# POWER_TS.net
KiCad netlist of a schematic drawn in Altium Designer
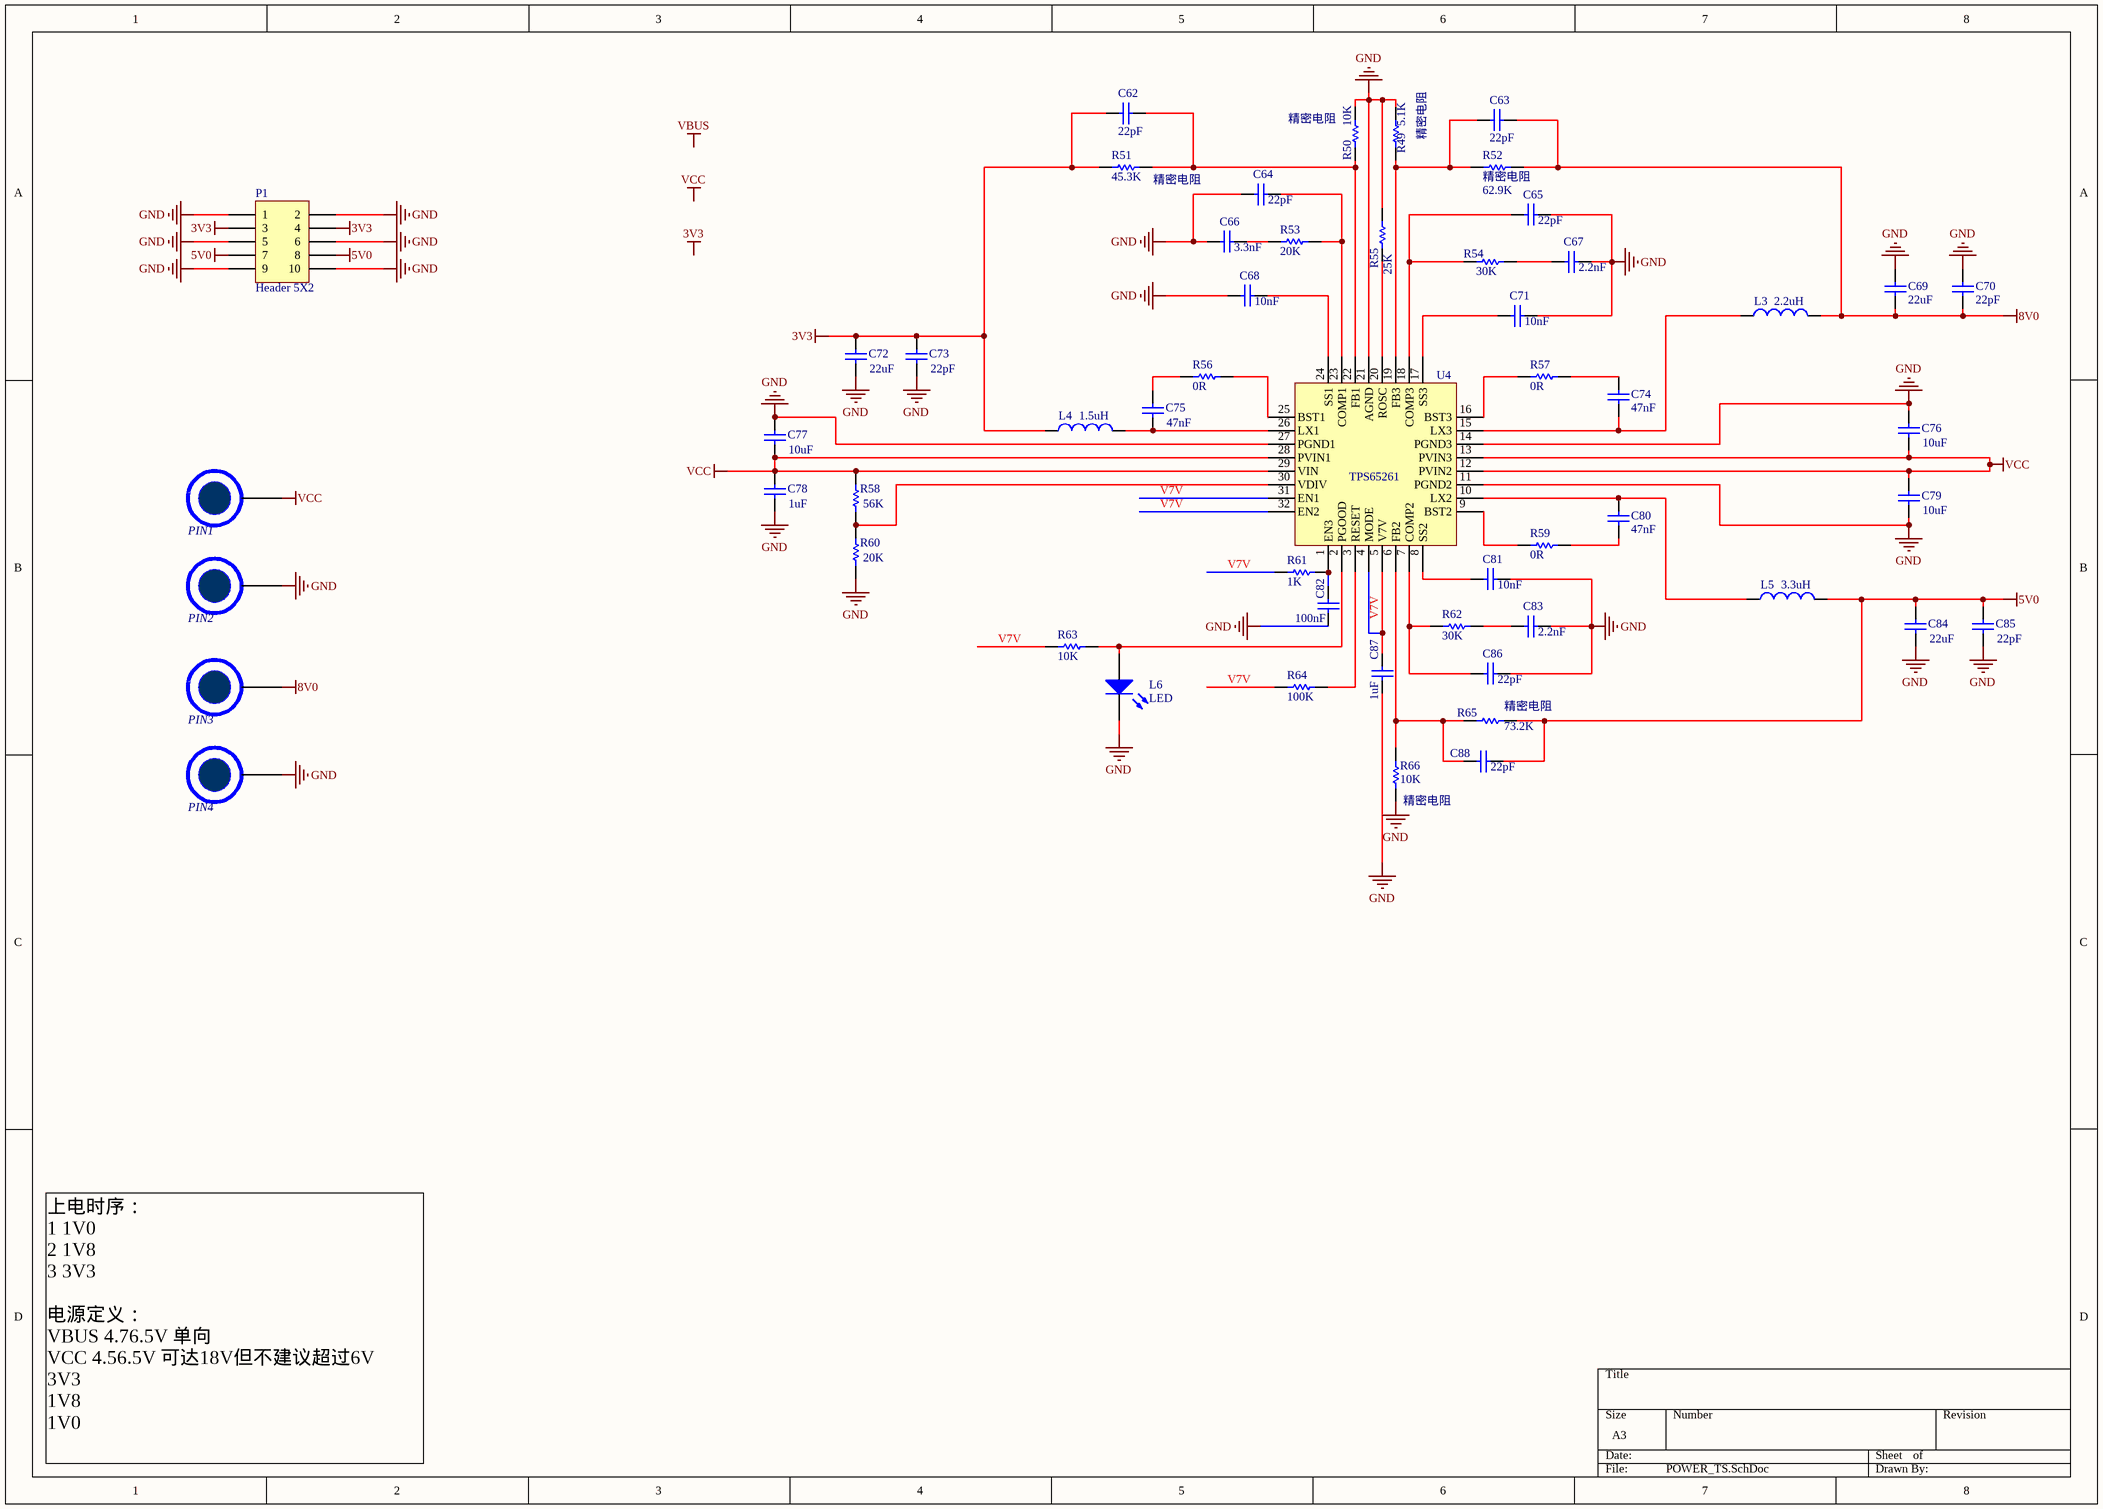
[diagram p0: POWER_TS.SchDoc]

(export (version "E")
  (design (tool "Eeschema 10.0.6"))
  (components
    (comp (ref "C62")
      (value "22pF")
      (footprint "0402")
      (description "贴片电容")
      (fields (field (name "Comment") "Cap") (field (name "PUBLISHER") "Altium Limited"))
      (libsource (lib "Sparks") (part "Cap"))
    )
    (comp (ref "C63")
      (value "22pF")
      (footprint "0402")
      (description "贴片电容")
      (fields (field (name "Comment") "Cap") (field (name "PUBLISHER") "Altium Limited"))
      (libsource (lib "Sparks") (part "Cap"))
    )
    (comp (ref "C64")
      (value "22pF")
      (footprint "0402")
      (description "贴片电容")
      (fields (field (name "Comment") "Cap") (field (name "PUBLISHER") "Altium Limited"))
      (libsource (lib "Sparks") (part "Cap"))
    )
    (comp (ref "C65")
      (value "22pF")
      (footprint "0402")
      (description "贴片电容")
      (fields (field (name "Comment") "Cap") (field (name "PUBLISHER") "Altium Limited"))
      (libsource (lib "Sparks") (part "Cap"))
    )
    (comp (ref "C66")
      (value "3.3nF")
      (footprint "0402")
      (description "贴片电容")
      (fields (field (name "Comment") "Cap") (field (name "PUBLISHER") "Altium Limited"))
      (libsource (lib "Sparks") (part "Cap"))
    )
    (comp (ref "C67")
      (value "2.2nF")
      (footprint "0402")
      (description "贴片电容")
      (fields (field (name "Comment") "Cap") (field (name "PUBLISHER") "Altium Limited"))
      (libsource (lib "Sparks") (part "Cap"))
    )
    (comp (ref "C68")
      (value "10nF")
      (footprint "0402")
      (description "贴片电容")
      (fields (field (name "Comment") "Cap") (field (name "PUBLISHER") "Altium Limited"))
      (libsource (lib "Sparks") (part "Cap"))
    )
    (comp (ref "C69")
      (value "22uF")
      (footprint "1206")
      (description "贴片电容")
      (fields (field (name "Comment") "Cap") (field (name "PUBLISHER") "Altium Limited"))
      (libsource (lib "Sparks") (part "Cap"))
    )
    (comp (ref "C70")
      (value "22pF")
      (footprint "0402")
      (description "贴片电容")
      (fields (field (name "Comment") "Cap") (field (name "PUBLISHER") "Altium Limited"))
      (libsource (lib "Sparks") (part "Cap"))
    )
    (comp (ref "C71")
      (value "10nF")
      (footprint "0402")
      (description "贴片电容")
      (fields (field (name "Comment") "Cap") (field (name "PUBLISHER") "Altium Limited"))
      (libsource (lib "Sparks") (part "Cap"))
    )
    (comp (ref "C72")
      (value "22uF")
      (footprint "1206")
      (description "贴片电容")
      (fields (field (name "Comment") "Cap") (field (name "PUBLISHER") "Altium Limited"))
      (libsource (lib "Sparks") (part "Cap"))
    )
    (comp (ref "C73")
      (value "22pF")
      (footprint "0402")
      (description "贴片电容")
      (fields (field (name "Comment") "Cap") (field (name "PUBLISHER") "Altium Limited"))
      (libsource (lib "Sparks") (part "Cap"))
    )
    (comp (ref "C74")
      (value "47nF")
      (footprint "0402")
      (description "贴片电容")
      (fields (field (name "Comment") "Cap") (field (name "PUBLISHER") "Altium Limited"))
      (libsource (lib "Sparks") (part "Cap"))
    )
    (comp (ref "C75")
      (value "47nF")
      (footprint "0402")
      (description "贴片电容")
      (fields (field (name "Comment") "Cap") (field (name "PUBLISHER") "Altium Limited"))
      (libsource (lib "Sparks") (part "Cap"))
    )
    (comp (ref "C76")
      (value "10uF")
      (footprint "1206")
      (description "贴片电容")
      (fields (field (name "Comment") "Cap") (field (name "PUBLISHER") "Altium Limited"))
      (libsource (lib "Sparks") (part "Cap"))
    )
    (comp (ref "C77")
      (value "10uF")
      (footprint "1206")
      (description "贴片电容")
      (fields (field (name "Comment") "Cap") (field (name "PUBLISHER") "Altium Limited"))
      (libsource (lib "Sparks") (part "Cap"))
    )
    (comp (ref "C78")
      (value "1uF")
      (footprint "1608[0603]")
      (description "贴片电容")
      (fields (field (name "Comment") "Cap") (field (name "PUBLISHER") "Altium Limited"))
      (libsource (lib "Sparks") (part "Cap"))
    )
    (comp (ref "C79")
      (value "10uF")
      (footprint "1206")
      (description "贴片电容")
      (fields (field (name "Comment") "Cap") (field (name "PUBLISHER") "Altium Limited"))
      (libsource (lib "Sparks") (part "Cap"))
    )
    (comp (ref "C80")
      (value "47nF")
      (footprint "0402")
      (description "贴片电容")
      (fields (field (name "Comment") "Cap") (field (name "PUBLISHER") "Altium Limited"))
      (libsource (lib "Sparks") (part "Cap"))
    )
    (comp (ref "C81")
      (value "10nF")
      (footprint "0402")
      (description "贴片电容")
      (fields (field (name "Comment") "Cap") (field (name "PUBLISHER") "Altium Limited"))
      (libsource (lib "Sparks") (part "Cap"))
    )
    (comp (ref "C82")
      (value "100nF")
      (footprint "0402")
      (description "贴片电容")
      (fields (field (name "Comment") "Cap") (field (name "PUBLISHER") "Altium Limited"))
      (libsource (lib "Sparks") (part "Cap"))
    )
    (comp (ref "C83")
      (value "2.2nF")
      (footprint "0402")
      (description "贴片电容")
      (fields (field (name "Comment") "Cap") (field (name "PUBLISHER") "Altium Limited"))
      (libsource (lib "Sparks") (part "Cap"))
    )
    (comp (ref "C84")
      (value "22uF")
      (footprint "1206")
      (description "贴片电容")
      (fields (field (name "Comment") "Cap") (field (name "PUBLISHER") "Altium Limited"))
      (libsource (lib "Sparks") (part "Cap"))
    )
    (comp (ref "C85")
      (value "22pF")
      (footprint "0402")
      (description "贴片电容")
      (fields (field (name "Comment") "Cap") (field (name "PUBLISHER") "Altium Limited"))
      (libsource (lib "Sparks") (part "Cap"))
    )
    (comp (ref "C86")
      (value "22pF")
      (footprint "0402")
      (description "贴片电容")
      (fields (field (name "Comment") "Cap") (field (name "PUBLISHER") "Altium Limited"))
      (libsource (lib "Sparks") (part "Cap"))
    )
    (comp (ref "C87")
      (value "1uF")
      (footprint "1608[0603]")
      (description "贴片电容")
      (fields (field (name "Comment") "Cap") (field (name "PUBLISHER") "Altium Limited"))
      (libsource (lib "Sparks") (part "Cap"))
    )
    (comp (ref "C88")
      (value "22pF")
      (footprint "0402")
      (description "贴片电容")
      (fields (field (name "Comment") "Cap") (field (name "PUBLISHER") "Altium Limited"))
      (libsource (lib "Sparks") (part "Cap"))
    )
    (comp (ref "L3")
      (value "2.2uH")
      (footprint "2220")
      (description "Inductor")
      (fields (field (name "PUBLISHER") "Altium Limited"))
      (libsource (lib "Miscellaneous Devices") (part "Inductor"))
    )
    (comp (ref "L4")
      (value "1.5uH")
      (footprint "C2012")
      (description "Inductor")
      (fields (field (name "PUBLISHER") "Altium Limited"))
      (libsource (lib "Miscellaneous Devices") (part "Inductor"))
    )
    (comp (ref "L5")
      (value "3.3uH")
      (footprint "C2012")
      (description "Inductor")
      (fields (field (name "PUBLISHER") "Altium Limited"))
      (libsource (lib "Miscellaneous Devices") (part "Inductor"))
    )
    (comp (ref "L6") (value "LED") (footprint "1608[0603]") (libsource (lib "Sparks") (part "LED")))
    (comp (ref "P1")
      (value "Header 5X2")
      (footprint "HDR2X5")
      (description "Header, 5-Pin, Dual row")
      (fields (field (name "PUBLISHER") "Altium Limited"))
      (libsource (lib "Sparks") (part "Header 5X2"))
    )
    (comp (ref "PIN1") (value "PIN") (footprint "PIN") (libsource (lib "2号库") (part "PIN")))
    (comp (ref "PIN2") (value "PIN") (footprint "PIN") (libsource (lib "2号库") (part "PIN")))
    (comp (ref "PIN3") (value "PIN") (footprint "PIN") (libsource (lib "2号库") (part "PIN")))
    (comp (ref "PIN4") (value "PIN") (footprint "PIN") (libsource (lib "2号库") (part "PIN")))
    (comp (ref "R49")
      (value "精密电阻")
      (footprint "1608[0603]")
      (description "贴片电阻")
      (fields (field (name "ALTIUM_VALUE") "5.1K") (field (name "PUBLISHER") "Altium Limited"))
      (libsource (lib "Sparks") (part "Res"))
    )
    (comp (ref "R50")
      (value "精密电阻")
      (footprint "1608[0603]")
      (description "贴片电阻")
      (fields (field (name "ALTIUM_VALUE") "10K") (field (name "PUBLISHER") "Altium Limited"))
      (libsource (lib "Sparks") (part "Res"))
    )
    (comp (ref "R51")
      (value "精密电阻")
      (footprint "R2012")
      (description "贴片电阻")
      (fields (field (name "ALTIUM_VALUE") "45.3K") (field (name "PUBLISHER") "Altium Limited"))
      (libsource (lib "Sparks") (part "Res"))
    )
    (comp (ref "R52")
      (value "精密电阻")
      (footprint "R2012")
      (description "贴片电阻")
      (fields (field (name "ALTIUM_VALUE") "62.9K") (field (name "PUBLISHER") "Altium Limited"))
      (libsource (lib "Sparks") (part "Res"))
    )
    (comp (ref "R53")
      (value "20K")
      (footprint "0402")
      (description "贴片电阻")
      (fields (field (name "Comment") "Res") (field (name "PUBLISHER") "Altium Limited"))
      (libsource (lib "Sparks") (part "Res"))
    )
    (comp (ref "R54")
      (value "30K")
      (footprint "0402")
      (description "贴片电阻")
      (fields (field (name "Comment") "Res") (field (name "PUBLISHER") "Altium Limited"))
      (libsource (lib "Sparks") (part "Res"))
    )
    (comp (ref "R55")
      (value "25K")
      (footprint "0402")
      (description "贴片电阻")
      (fields (field (name "Comment") "Res") (field (name "PUBLISHER") "Altium Limited"))
      (libsource (lib "Sparks") (part "Res"))
    )
    (comp (ref "R56")
      (value "0R")
      (footprint "0402")
      (description "贴片电阻")
      (fields (field (name "Comment") "Res") (field (name "PUBLISHER") "Altium Limited"))
      (libsource (lib "Sparks") (part "Res"))
    )
    (comp (ref "R57")
      (value "0R")
      (footprint "0402")
      (description "贴片电阻")
      (fields (field (name "Comment") "Res") (field (name "PUBLISHER") "Altium Limited"))
      (libsource (lib "Sparks") (part "Res"))
    )
    (comp (ref "R58")
      (value "56K")
      (footprint "0402")
      (description "贴片电阻")
      (fields (field (name "Comment") "Res") (field (name "PUBLISHER") "Altium Limited"))
      (libsource (lib "Sparks") (part "Res"))
    )
    (comp (ref "R59")
      (value "0R")
      (footprint "0402")
      (description "贴片电阻")
      (fields (field (name "Comment") "Res") (field (name "PUBLISHER") "Altium Limited"))
      (libsource (lib "Sparks") (part "Res"))
    )
    (comp (ref "R60")
      (value "20K")
      (footprint "0402")
      (description "贴片电阻")
      (fields (field (name "Comment") "Res") (field (name "PUBLISHER") "Altium Limited"))
      (libsource (lib "Sparks") (part "Res"))
    )
    (comp (ref "R61")
      (value "1K")
      (footprint "0402")
      (description "贴片电阻")
      (fields (field (name "Comment") "Res") (field (name "PUBLISHER") "Altium Limited"))
      (libsource (lib "Sparks") (part "Res"))
    )
    (comp (ref "R62")
      (value "30K")
      (footprint "0402")
      (description "贴片电阻")
      (fields (field (name "Comment") "Res") (field (name "PUBLISHER") "Altium Limited"))
      (libsource (lib "Sparks") (part "Res"))
    )
    (comp (ref "R63")
      (value "10K")
      (footprint "0402")
      (description "贴片电阻")
      (fields (field (name "Comment") "Res") (field (name "PUBLISHER") "Altium Limited"))
      (libsource (lib "Sparks") (part "Res"))
    )
    (comp (ref "R64")
      (value "100K")
      (footprint "0402")
      (description "贴片电阻")
      (fields (field (name "Comment") "Res") (field (name "PUBLISHER") "Altium Limited"))
      (libsource (lib "Sparks") (part "Res"))
    )
    (comp (ref "R65")
      (value "精密电阻")
      (footprint "1608[0603]")
      (description "贴片电阻")
      (fields (field (name "ALTIUM_VALUE") "73.2K") (field (name "PUBLISHER") "Altium Limited"))
      (libsource (lib "Sparks") (part "Res"))
    )
    (comp (ref "R66")
      (value "精密电阻")
      (footprint "1608[0603]")
      (description "贴片电阻")
      (fields (field (name "ALTIUM_VALUE") "10K") (field (name "PUBLISHER") "Altium Limited"))
      (libsource (lib "Sparks") (part "Res"))
    )
    (comp (ref "U4")
      (value "TPS65261")
      (footprint "QFN50P500X500X100_HS-33N")
      (libsource (lib "2号库") (part "TPS65261"))
    )
  )
  (nets
    (net (code "1") (name "/V7V") (class "Default")
      (node (ref "C87") (pin "2") (pinfunction "2_2") (pintype "passive"))
      (node (ref "R61") (pin "1") (pinfunction "1_1") (pintype "passive"))
      (node (ref "R63") (pin "2") (pinfunction "2_2") (pintype "passive"))
      (node (ref "R64") (pin "2") (pinfunction "2_2") (pintype "passive"))
      (node (ref "U4") (pin "31") (pinfunction "EN1_31") (pintype "passive"))
      (node (ref "U4") (pin "32") (pinfunction "EN2_32") (pintype "passive"))
      (node (ref "U4") (pin "4") (pinfunction "MODE_4") (pintype "passive"))
      (node (ref "U4") (pin "5") (pinfunction "V7V_5") (pintype "passive"))
    )
    (net (code "2") (name "3V3") (class "Default")
      (node (ref "C62") (pin "2") (pinfunction "2_2") (pintype "passive"))
      (node (ref "C72") (pin "2") (pinfunction "2_2") (pintype "passive"))
      (node (ref "C73") (pin "2") (pinfunction "2_2") (pintype "passive"))
      (node (ref "L4") (pin "1") (pinfunction "1_1") (pintype "passive"))
      (node (ref "P1") (pin "3") (pinfunction "3_3") (pintype "passive"))
      (node (ref "P1") (pin "4") (pinfunction "4_4") (pintype "passive"))
      (node (ref "R51") (pin "2") (pinfunction "2_2") (pintype "passive"))
    )
    (net (code "3") (name "5V0") (class "Default")
      (node (ref "C84") (pin "2") (pinfunction "2_2") (pintype "passive"))
      (node (ref "C85") (pin "2") (pinfunction "2_2") (pintype "passive"))
      (node (ref "C88") (pin "2") (pinfunction "2_2") (pintype "passive"))
      (node (ref "L5") (pin "2") (pinfunction "2_2") (pintype "passive"))
      (node (ref "P1") (pin "7") (pinfunction "7_7") (pintype "passive"))
      (node (ref "P1") (pin "8") (pinfunction "8_8") (pintype "passive"))
      (node (ref "R65") (pin "1") (pinfunction "1_1") (pintype "passive"))
    )
    (net (code "4") (name "8V0") (class "Default")
      (node (ref "C63") (pin "1") (pinfunction "1_1") (pintype "passive"))
      (node (ref "C69") (pin "2") (pinfunction "2_2") (pintype "passive"))
      (node (ref "C70") (pin "2") (pinfunction "2_2") (pintype "passive"))
      (node (ref "L3") (pin "2") (pinfunction "2_2") (pintype "passive"))
      (node (ref "PIN3") (pin "1") (pinfunction "PIN_1") (pintype "passive"))
      (node (ref "R52") (pin "1") (pinfunction "1_1") (pintype "passive"))
    )
    (net (code "5") (name "GND") (class "Default")
      (node (ref "C64") (pin "1") (pinfunction "1_1") (pintype "passive"))
      (node (ref "C65") (pin "2") (pinfunction "2_2") (pintype "passive"))
      (node (ref "C66") (pin "1") (pinfunction "1_1") (pintype "passive"))
      (node (ref "C67") (pin "2") (pinfunction "2_2") (pintype "passive"))
      (node (ref "C68") (pin "1") (pinfunction "1_1") (pintype "passive"))
      (node (ref "C69") (pin "1") (pinfunction "1_1") (pintype "passive"))
      (node (ref "C70") (pin "1") (pinfunction "1_1") (pintype "passive"))
      (node (ref "C71") (pin "2") (pinfunction "2_2") (pintype "passive"))
      (node (ref "C72") (pin "1") (pinfunction "1_1") (pintype "passive"))
      (node (ref "C73") (pin "1") (pinfunction "1_1") (pintype "passive"))
      (node (ref "C76") (pin "2") (pinfunction "2_2") (pintype "passive"))
      (node (ref "C77") (pin "2") (pinfunction "2_2") (pintype "passive"))
      (node (ref "C78") (pin "1") (pinfunction "1_1") (pintype "passive"))
      (node (ref "C79") (pin "1") (pinfunction "1_1") (pintype "passive"))
      (node (ref "C81") (pin "1") (pinfunction "1_1") (pintype "passive"))
      (node (ref "C82") (pin "1") (pinfunction "1_1") (pintype "passive"))
      (node (ref "C83") (pin "1") (pinfunction "1_1") (pintype "passive"))
      (node (ref "C84") (pin "1") (pinfunction "1_1") (pintype "passive"))
      (node (ref "C85") (pin "1") (pinfunction "1_1") (pintype "passive"))
      (node (ref "C86") (pin "2") (pinfunction "2_2") (pintype "passive"))
      (node (ref "C87") (pin "1") (pinfunction "1_1") (pintype "passive"))
      (node (ref "L6") (pin "2") (pinfunction "K_2") (pintype "passive"))
      (node (ref "P1") (pin "1") (pinfunction "1_1") (pintype "passive"))
      (node (ref "P1") (pin "10") (pinfunction "10_10") (pintype "passive"))
      (node (ref "P1") (pin "2") (pinfunction "2_2") (pintype "passive"))
      (node (ref "P1") (pin "5") (pinfunction "5_5") (pintype "passive"))
      (node (ref "P1") (pin "6") (pinfunction "6_6") (pintype "passive"))
      (node (ref "P1") (pin "9") (pinfunction "9_9") (pintype "passive"))
      (node (ref "PIN2") (pin "1") (pinfunction "PIN_1") (pintype "passive"))
      (node (ref "PIN4") (pin "1") (pinfunction "PIN_1") (pintype "passive"))
      (node (ref "R49") (pin "1") (pinfunction "1_1") (pintype "passive"))
      (node (ref "R50") (pin "1") (pinfunction "1_1") (pintype "passive"))
      (node (ref "R55") (pin "2") (pinfunction "2_2") (pintype "passive"))
      (node (ref "R60") (pin "1") (pinfunction "1_1") (pintype "passive"))
      (node (ref "R66") (pin "1") (pinfunction "1_1") (pintype "passive"))
      (node (ref "U4") (pin "11") (pinfunction "PGND2_11") (pintype "passive"))
      (node (ref "U4") (pin "14") (pinfunction "PGND3_14") (pintype "passive"))
      (node (ref "U4") (pin "21") (pinfunction "AGND_21") (pintype "passive"))
      (node (ref "U4") (pin "27") (pinfunction "PGND1_27") (pintype "passive"))
    )
    (net (code "6") (name "Net-(C66-Pad2)") (class "Default")
      (node (ref "C66") (pin "2") (pinfunction "2_2") (pintype "passive"))
      (node (ref "R53") (pin "1") (pinfunction "1_1") (pintype "passive"))
    )
    (net (code "7") (name "Net-(C67-Pad1)") (class "Default")
      (node (ref "C67") (pin "1") (pinfunction "1_1") (pintype "passive"))
      (node (ref "R54") (pin "2") (pinfunction "2_2") (pintype "passive"))
    )
    (net (code "8") (name "Net-(C74-Pad1)") (class "Default")
      (node (ref "C74") (pin "1") (pinfunction "1_1") (pintype "passive"))
      (node (ref "R57") (pin "1") (pinfunction "1_1") (pintype "passive"))
    )
    (net (code "9") (name "Net-(C75-Pad2)") (class "Default")
      (node (ref "C75") (pin "2") (pinfunction "2_2") (pintype "passive"))
      (node (ref "R56") (pin "2") (pinfunction "2_2") (pintype "passive"))
    )
    (net (code "10") (name "Net-(C80-Pad2)") (class "Default")
      (node (ref "C80") (pin "2") (pinfunction "2_2") (pintype "passive"))
      (node (ref "R59") (pin "1") (pinfunction "1_1") (pintype "passive"))
    )
    (net (code "11") (name "Net-(C83-Pad2)") (class "Default")
      (node (ref "C83") (pin "2") (pinfunction "2_2") (pintype "passive"))
      (node (ref "R62") (pin "2") (pinfunction "2_2") (pintype "passive"))
    )
    (net (code "12") (name "Net-(L6-A)") (class "Default")
      (node (ref "L6") (pin "1") (pinfunction "A_1") (pintype "passive"))
      (node (ref "R63") (pin "1") (pinfunction "1_1") (pintype "passive"))
      (node (ref "U4") (pin "2") (pinfunction "PGOOD_2") (pintype "passive"))
    )
    (net (code "13") (name "Net-(U4-BST1)") (class "Default")
      (node (ref "R56") (pin "1") (pinfunction "1_1") (pintype "passive"))
      (node (ref "U4") (pin "25") (pinfunction "BST1_25") (pintype "passive"))
    )
    (net (code "14") (name "Net-(U4-BST2)") (class "Default")
      (node (ref "R59") (pin "2") (pinfunction "2_2") (pintype "passive"))
      (node (ref "U4") (pin "9") (pinfunction "BST2_9") (pintype "passive"))
    )
    (net (code "15") (name "Net-(U4-BST3)") (class "Default")
      (node (ref "R57") (pin "2") (pinfunction "2_2") (pintype "passive"))
      (node (ref "U4") (pin "16") (pinfunction "BST3_16") (pintype "passive"))
    )
    (net (code "16") (name "Net-(U4-COMP1)") (class "Default")
      (node (ref "C64") (pin "2") (pinfunction "2_2") (pintype "passive"))
      (node (ref "R53") (pin "2") (pinfunction "2_2") (pintype "passive"))
      (node (ref "U4") (pin "23") (pinfunction "COMP1_23") (pintype "passive"))
    )
    (net (code "17") (name "Net-(U4-COMP2)") (class "Default")
      (node (ref "C86") (pin "1") (pinfunction "1_1") (pintype "passive"))
      (node (ref "R62") (pin "1") (pinfunction "1_1") (pintype "passive"))
      (node (ref "U4") (pin "7") (pinfunction "COMP2_7") (pintype "passive"))
    )
    (net (code "18") (name "Net-(U4-COMP3)") (class "Default")
      (node (ref "C65") (pin "1") (pinfunction "1_1") (pintype "passive"))
      (node (ref "R54") (pin "1") (pinfunction "1_1") (pintype "passive"))
      (node (ref "U4") (pin "18") (pinfunction "COMP3_18") (pintype "passive"))
    )
    (net (code "19") (name "Net-(U4-EN3)") (class "Default")
      (node (ref "C82") (pin "2") (pinfunction "2_2") (pintype "passive"))
      (node (ref "R61") (pin "2") (pinfunction "2_2") (pintype "passive"))
      (node (ref "U4") (pin "1") (pinfunction "EN3_1") (pintype "passive"))
    )
    (net (code "20") (name "Net-(U4-FB1)") (class "Default")
      (node (ref "C62") (pin "1") (pinfunction "1_1") (pintype "passive"))
      (node (ref "R50") (pin "2") (pinfunction "2_2") (pintype "passive"))
      (node (ref "R51") (pin "1") (pinfunction "1_1") (pintype "passive"))
      (node (ref "U4") (pin "22") (pinfunction "FB1_22") (pintype "passive"))
    )
    (net (code "21") (name "Net-(U4-FB2)") (class "Default")
      (node (ref "C88") (pin "1") (pinfunction "1_1") (pintype "passive"))
      (node (ref "R65") (pin "2") (pinfunction "2_2") (pintype "passive"))
      (node (ref "R66") (pin "2") (pinfunction "2_2") (pintype "passive"))
      (node (ref "U4") (pin "6") (pinfunction "FB2_6") (pintype "passive"))
    )
    (net (code "22") (name "Net-(U4-FB3)") (class "Default")
      (node (ref "C63") (pin "2") (pinfunction "2_2") (pintype "passive"))
      (node (ref "R49") (pin "2") (pinfunction "2_2") (pintype "passive"))
      (node (ref "R52") (pin "2") (pinfunction "2_2") (pintype "passive"))
      (node (ref "U4") (pin "19") (pinfunction "FB3_19") (pintype "passive"))
    )
    (net (code "23") (name "Net-(U4-LX1)") (class "Default")
      (node (ref "C75") (pin "1") (pinfunction "1_1") (pintype "passive"))
      (node (ref "L4") (pin "2") (pinfunction "2_2") (pintype "passive"))
      (node (ref "U4") (pin "26") (pinfunction "LX1_26") (pintype "passive"))
    )
    (net (code "24") (name "Net-(U4-LX2)") (class "Default")
      (node (ref "C80") (pin "1") (pinfunction "1_1") (pintype "passive"))
      (node (ref "L5") (pin "1") (pinfunction "1_1") (pintype "passive"))
      (node (ref "U4") (pin "10") (pinfunction "LX2_10") (pintype "passive"))
    )
    (net (code "25") (name "Net-(U4-LX3)") (class "Default")
      (node (ref "C74") (pin "2") (pinfunction "2_2") (pintype "passive"))
      (node (ref "L3") (pin "1") (pinfunction "1_1") (pintype "passive"))
      (node (ref "U4") (pin "15") (pinfunction "LX3_15") (pintype "passive"))
    )
    (net (code "26") (name "Net-(U4-RESET)") (class "Default")
      (node (ref "R64") (pin "1") (pinfunction "1_1") (pintype "passive"))
      (node (ref "U4") (pin "3") (pinfunction "RESET_3") (pintype "passive"))
    )
    (net (code "27") (name "Net-(U4-ROSC)") (class "Default")
      (node (ref "R55") (pin "1") (pinfunction "1_1") (pintype "passive"))
      (node (ref "U4") (pin "20") (pinfunction "ROSC_20") (pintype "passive"))
    )
    (net (code "28") (name "Net-(U4-SS1)") (class "Default")
      (node (ref "C68") (pin "2") (pinfunction "2_2") (pintype "passive"))
      (node (ref "U4") (pin "24") (pinfunction "SS1_24") (pintype "passive"))
    )
    (net (code "29") (name "Net-(U4-SS2)") (class "Default")
      (node (ref "C81") (pin "2") (pinfunction "2_2") (pintype "passive"))
      (node (ref "U4") (pin "8") (pinfunction "SS2_8") (pintype "passive"))
    )
    (net (code "30") (name "Net-(U4-SS3)") (class "Default")
      (node (ref "C71") (pin "1") (pinfunction "1_1") (pintype "passive"))
      (node (ref "U4") (pin "17") (pinfunction "SS3_17") (pintype "passive"))
    )
    (net (code "31") (name "Net-(U4-VDIV)") (class "Default")
      (node (ref "R58") (pin "1") (pinfunction "1_1") (pintype "passive"))
      (node (ref "R60") (pin "2") (pinfunction "2_2") (pintype "passive"))
      (node (ref "U4") (pin "30") (pinfunction "VDIV_30") (pintype "passive"))
    )
    (net (code "33") (name "VCC") (class "Default")
      (node (ref "C76") (pin "1") (pinfunction "1_1") (pintype "passive"))
      (node (ref "C77") (pin "1") (pinfunction "1_1") (pintype "passive"))
      (node (ref "C78") (pin "2") (pinfunction "2_2") (pintype "passive"))
      (node (ref "C79") (pin "2") (pinfunction "2_2") (pintype "passive"))
      (node (ref "PIN1") (pin "1") (pinfunction "PIN_1") (pintype "passive"))
      (node (ref "R58") (pin "2") (pinfunction "2_2") (pintype "passive"))
      (node (ref "U4") (pin "12") (pinfunction "PVIN2_12") (pintype "passive"))
      (node (ref "U4") (pin "13") (pinfunction "PVIN3_13") (pintype "passive"))
      (node (ref "U4") (pin "28") (pinfunction "PVIN1_28") (pintype "passive"))
      (node (ref "U4") (pin "29") (pinfunction "VIN_29") (pintype "passive"))
    )
  )
)
